# dtmf_v1_2.net
KiCad netlist of a schematic drawn in EAGLE
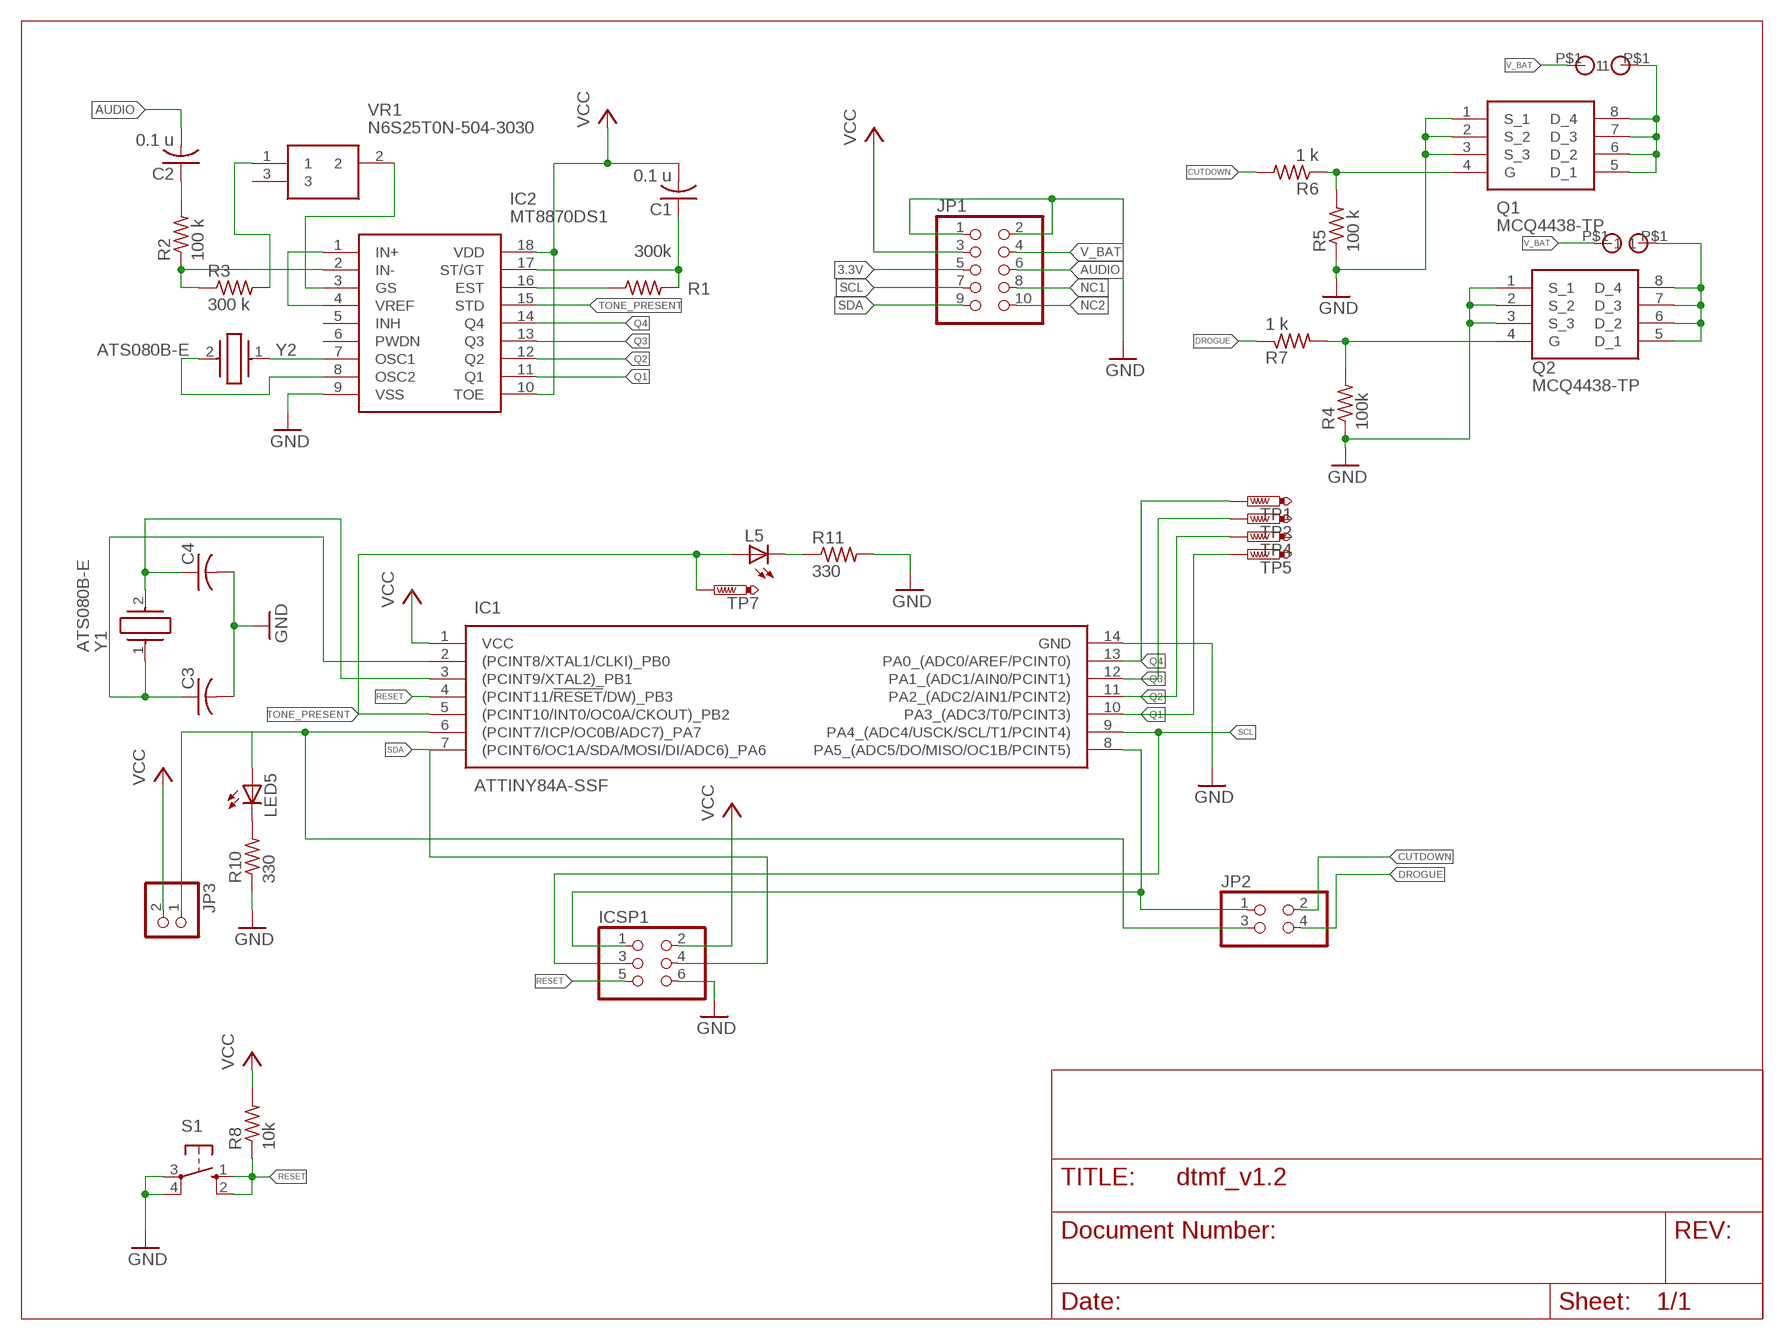
[diagram p0: schematic, sheet 1]

(export (version "E")
  (design (tool "Eeschema 10.0.6"))
  (components
    (comp (ref "C1")
      (value "0.1 u")
      (footprint "eagle-import:C0603")
      (libsource (lib "eagle-import") (part "C-USC0603"))
    )
    (comp (ref "C2")
      (value "0.1 u")
      (footprint "eagle-import:C0603")
      (libsource (lib "eagle-import") (part "C-USC0603"))
    )
    (comp (ref "C3")
      (value "C-USC0805")
      (footprint "eagle-import:C0805")
      (libsource (lib "eagle-import") (part "C-USC0805"))
    )
    (comp (ref "C4")
      (value "C-USC0805")
      (footprint "eagle-import:C0805")
      (libsource (lib "eagle-import") (part "C-USC0805"))
    )
    (comp (ref "IC1")
      (value "ATTINY84A-SSF")
      (footprint "eagle-import:SOIC127P600X175-14N")
      (fields (field (name "MOUSER_PART_NUMBER") "556-ATTINY84A-SSF"))
      (libsource (lib "eagle-import") (part "ATTINY84A-SSF"))
    )
    (comp (ref "IC2")
      (value "MT8870DS1")
      (footprint "eagle-import:SOIC127P1032X265-18N")
      (fields (field (name "MOUSER_PART_NUMBER") "494-MT8870DS1"))
      (libsource (lib "eagle-import") (part "MT8870DS1"))
    )
    (comp (ref "ICSP1")
      (value "PINHD-2X3")
      (footprint "eagle-import:2X03")
      (libsource (lib "eagle-import") (part "PINHD-2X3"))
    )
    (comp (ref "JP1")
      (value "PINHD-2X5")
      (footprint "eagle-import:2X05")
      (libsource (lib "eagle-import") (part "PINHD-2X5"))
    )
    (comp (ref "JP2")
      (value "PINHD-2X2")
      (footprint "eagle-import:2X02")
      (libsource (lib "eagle-import") (part "PINHD-2X2"))
    )
    (comp (ref "JP3")
      (value "PINHD-1X2")
      (footprint "eagle-import:1X02")
      (libsource (lib "eagle-import") (part "PINHD-1X2"))
    )
    (comp (ref "L5")
      (value "LEDCHIP-LED0805")
      (footprint "eagle-import:CHIP-LED0805")
      (libsource (lib "eagle-import") (part "LEDCHIP-LED0805"))
    )
    (comp (ref "LED5")
      (value "LEDCHIP-LED0805")
      (footprint "eagle-import:CHIP-LED0805")
      (libsource (lib "eagle-import") (part "LEDCHIP-LED0805"))
    )
    (comp (ref "Q1")
      (value "MCQ4438-TP")
      (footprint "eagle-import:SOIC127P600X175-8N")
      (libsource (lib "eagle-import") (part "MCQ4438-TP"))
    )
    (comp (ref "Q2")
      (value "MCQ4438-TP")
      (footprint "eagle-import:SOIC127P600X175-8N")
      (libsource (lib "eagle-import") (part "MCQ4438-TP"))
    )
    (comp (ref "R1")
      (value "300k")
      (footprint "eagle-import:M0805")
      (libsource (lib "eagle-import") (part "R-US_M0805"))
    )
    (comp (ref "R2")
      (value "100 k")
      (footprint "eagle-import:M0805")
      (libsource (lib "eagle-import") (part "R-US_M0805"))
    )
    (comp (ref "R3")
      (value "300 k")
      (footprint "eagle-import:M0805")
      (libsource (lib "eagle-import") (part "R-US_M0805"))
    )
    (comp (ref "R4")
      (value "100k")
      (footprint "eagle-import:M0805")
      (libsource (lib "eagle-import") (part "R-US_M0805"))
    )
    (comp (ref "R5")
      (value "100 k")
      (footprint "eagle-import:M0805")
      (libsource (lib "eagle-import") (part "R-US_M0805"))
    )
    (comp (ref "R6")
      (value "1 k")
      (footprint "eagle-import:M0805")
      (libsource (lib "eagle-import") (part "R-US_M0805"))
    )
    (comp (ref "R7")
      (value "1 k")
      (footprint "eagle-import:M0805")
      (libsource (lib "eagle-import") (part "R-US_M0805"))
    )
    (comp (ref "R8")
      (value "10k")
      (footprint "eagle-import:0207_10")
      (libsource (lib "eagle-import") (part "R-US_0207/10"))
    )
    (comp (ref "R10")
      (value "330")
      (footprint "eagle-import:M0805")
      (libsource (lib "eagle-import") (part "R-US_M0805"))
    )
    (comp (ref "R11")
      (value "330")
      (footprint "eagle-import:M0805")
      (libsource (lib "eagle-import") (part "R-US_M0805"))
    )
    (comp (ref "S1")
      (value "10-XX")
      (footprint "eagle-import:B3F-10XX")
      (fields (field (name "MPN") "B3F-1000"))
      (libsource (lib "eagle-import") (part "10-XX"))
    )
    (comp (ref "TP1")
      (value "PTR1B1,27")
      (footprint "eagle-import:B1,27")
      (libsource (lib "eagle-import") (part "PTR1B1,27"))
    )
    (comp (ref "TP2")
      (value "PTR1B1,27")
      (footprint "eagle-import:B1,27")
      (libsource (lib "eagle-import") (part "PTR1B1,27"))
    )
    (comp (ref "TP4")
      (value "PTR1B1,27")
      (footprint "eagle-import:B1,27")
      (libsource (lib "eagle-import") (part "PTR1B1,27"))
    )
    (comp (ref "TP5")
      (value "PTR1B1,27")
      (footprint "eagle-import:B1,27")
      (libsource (lib "eagle-import") (part "PTR1B1,27"))
    )
    (comp (ref "TP7")
      (value "PTR1B1,27")
      (footprint "eagle-import:B1,27")
      (libsource (lib "eagle-import") (part "PTR1B1,27"))
    )
    (comp (ref "U$1")
      (value "M3_HOLE")
      (footprint "eagle-import:MOUNTING_PAD")
      (libsource (lib "eagle-import") (part "M3_HOLE"))
    )
    (comp (ref "U$2")
      (value "M3_HOLE")
      (footprint "eagle-import:MOUNTING_PAD")
      (libsource (lib "eagle-import") (part "M3_HOLE"))
    )
    (comp (ref "U$3")
      (value "M3_HOLE")
      (footprint "eagle-import:MOUNTING_PAD")
      (libsource (lib "eagle-import") (part "M3_HOLE"))
    )
    (comp (ref "U$4")
      (value "M3_HOLE")
      (footprint "eagle-import:MOUNTING_PAD")
      (libsource (lib "eagle-import") (part "M3_HOLE"))
    )
    (comp (ref "VR1")
      (value "N6S25T0N-504-3030")
      (footprint "eagle-import:N6S25T0N5043030")
      (fields (field (name "MOUSER_PART_NUMBER") "531-N6S25T0N5043030"))
      (libsource (lib "eagle-import") (part "N6S25T0N-504-3030"))
    )
    (comp (ref "Y1")
      (value "ATS080B-E")
      (footprint "eagle-import:ATS080BE")
      (fields (field (name "MOUSER_PART_NUMBER") "774-ATS080B-E"))
      (libsource (lib "eagle-import") (part "ATS080B-E"))
    )
    (comp (ref "Y2")
      (value "ATS080B-E")
      (footprint "eagle-import:ATS080BE")
      (fields (field (name "MOUSER_PART_NUMBER") "774-ATS080B-E"))
      (libsource (lib "eagle-import") (part "ATS080B-E"))
    )
  )
  (nets
    (net (code "1") (name "3.3V") (class "Default")
      (node (ref "JP1") (pin "5") (pinfunction "5_5") (pintype "passive"))
    )
    (net (code "2") (name "AUDIO") (class "Default")
      (node (ref "C2") (pin "2") (pinfunction "2_2") (pintype "passive"))
      (node (ref "JP1") (pin "6") (pinfunction "6_6") (pintype "passive"))
    )
    (net (code "3") (name "CUTDOWN") (class "Default")
      (node (ref "JP2") (pin "2") (pinfunction "2_2") (pintype "passive"))
      (node (ref "R6") (pin "2") (pinfunction "2_2") (pintype "passive"))
    )
    (net (code "4") (name "DROGUE") (class "Default")
      (node (ref "JP2") (pin "4") (pinfunction "4_4") (pintype "passive"))
      (node (ref "R7") (pin "1") (pinfunction "1_1") (pintype "passive"))
    )
    (net (code "5") (name "GND") (class "Default")
      (node (ref "C3") (pin "2") (pinfunction "2_2") (pintype "passive"))
      (node (ref "C4") (pin "2") (pinfunction "2_2") (pintype "passive"))
      (node (ref "IC1") (pin "14") (pinfunction "GND_14") (pintype "bidirectional"))
      (node (ref "IC2") (pin "9") (pinfunction "VSS_9") (pintype "bidirectional"))
      (node (ref "ICSP1") (pin "6") (pinfunction "6_6") (pintype "passive"))
      (node (ref "JP1") (pin "1") (pinfunction "1_1") (pintype "passive"))
      (node (ref "JP1") (pin "2") (pinfunction "2_2") (pintype "passive"))
      (node (ref "Q1") (pin "1") (pinfunction "S_1_1") (pintype "bidirectional"))
      (node (ref "Q1") (pin "2") (pinfunction "S_2_2") (pintype "bidirectional"))
      (node (ref "Q1") (pin "3") (pinfunction "S_3_3") (pintype "bidirectional"))
      (node (ref "Q2") (pin "1") (pinfunction "S_1_1") (pintype "bidirectional"))
      (node (ref "Q2") (pin "2") (pinfunction "S_2_2") (pintype "bidirectional"))
      (node (ref "Q2") (pin "3") (pinfunction "S_3_3") (pintype "bidirectional"))
      (node (ref "R10") (pin "1") (pinfunction "1_1") (pintype "passive"))
      (node (ref "R11") (pin "2") (pinfunction "2_2") (pintype "passive"))
      (node (ref "R4") (pin "1") (pinfunction "1_1") (pintype "passive"))
      (node (ref "R5") (pin "1") (pinfunction "1_1") (pintype "passive"))
      (node (ref "S1") (pin "3") (pinfunction "P_3") (pintype "passive"))
      (node (ref "S1") (pin "4") (pinfunction "P1_4") (pintype "passive"))
    )
    (net (code "6") (name "NC1") (class "Default")
      (node (ref "JP1") (pin "8") (pinfunction "8_8") (pintype "passive"))
    )
    (net (code "7") (name "NC2") (class "Default")
      (node (ref "JP1") (pin "10") (pinfunction "10_10") (pintype "passive"))
    )
    (net (code "8") (name "Net-(C2-Pad1)") (class "Default")
      (node (ref "C2") (pin "1") (pinfunction "1_1") (pintype "passive"))
      (node (ref "R2") (pin "2") (pinfunction "2_2") (pintype "passive"))
    )
    (net (code "9") (name "Net-(IC1-(PCINT7{slash}ICP{slash}OC0B{slash}ADC7)_PA7)") (class "Default")
      (node (ref "IC1") (pin "6") (pinfunction "(PCINT7/ICP/OC0B/ADC7)_PA7_6") (pintype "bidirectional"))
      (node (ref "JP2") (pin "3") (pinfunction "3_3") (pintype "passive"))
      (node (ref "JP3") (pin "1") (pinfunction "1_1") (pintype "passive"))
      (node (ref "LED5") (pin "A") (pinfunction "A_A") (pintype "passive"))
    )
    (net (code "10") (name "Net-(IC1-(PCINT8{slash}XTAL1{slash}CLKI)_PB0)") (class "Default")
      (node (ref "C3") (pin "1") (pinfunction "1_1") (pintype "passive"))
      (node (ref "IC1") (pin "2") (pinfunction "(PCINT8/XTAL1/CLKI)_PB0_2") (pintype "bidirectional"))
      (node (ref "Y1") (pin "1") (pinfunction "1_1") (pintype "bidirectional"))
    )
    (net (code "11") (name "Net-(IC1-(PCINT9{slash}XTAL2)_PB1)") (class "Default")
      (node (ref "C4") (pin "1") (pinfunction "1_1") (pintype "passive"))
      (node (ref "IC1") (pin "3") (pinfunction "(PCINT9/XTAL2)_PB1_3") (pintype "bidirectional"))
      (node (ref "Y1") (pin "2") (pinfunction "2_2") (pintype "bidirectional"))
    )
    (net (code "12") (name "Net-(IC1-PA5_(ADC5{slash}DO{slash}MISO{slash}OC1B{slash}PCINT5))") (class "Default")
      (node (ref "IC1") (pin "8") (pinfunction "PA5_(ADC5/DO/MISO/OC1B/PCINT5)_8") (pintype "bidirectional"))
      (node (ref "ICSP1") (pin "1") (pinfunction "1_1") (pintype "passive"))
      (node (ref "JP2") (pin "1") (pinfunction "1_1") (pintype "passive"))
    )
    (net (code "13") (name "Net-(IC2-EST)") (class "Default")
      (node (ref "IC2") (pin "16") (pinfunction "EST_16") (pintype "bidirectional"))
      (node (ref "R1") (pin "1") (pinfunction "1_1") (pintype "passive"))
    )
    (net (code "14") (name "Net-(IC2-GS)") (class "Default")
      (node (ref "IC2") (pin "3") (pinfunction "GS_3") (pintype "bidirectional"))
      (node (ref "VR1") (pin "2") (pinfunction "2_2") (pintype "bidirectional"))
    )
    (net (code "15") (name "Net-(IC2-IN+)") (class "Default")
      (node (ref "IC2") (pin "1") (pinfunction "IN+_1") (pintype "bidirectional"))
      (node (ref "IC2") (pin "4") (pinfunction "VREF_4") (pintype "bidirectional"))
    )
    (net (code "16") (name "Net-(IC2-IN-)") (class "Default")
      (node (ref "IC2") (pin "2") (pinfunction "IN-_2") (pintype "bidirectional"))
      (node (ref "R2") (pin "1") (pinfunction "1_1") (pintype "passive"))
      (node (ref "R3") (pin "1") (pinfunction "1_1") (pintype "passive"))
    )
    (net (code "17") (name "Net-(IC2-OSC1)") (class "Default")
      (node (ref "IC2") (pin "7") (pinfunction "OSC1_7") (pintype "bidirectional"))
      (node (ref "Y2") (pin "1") (pinfunction "1_1") (pintype "bidirectional"))
    )
    (net (code "18") (name "Net-(IC2-OSC2)") (class "Default")
      (node (ref "IC2") (pin "8") (pinfunction "OSC2_8") (pintype "bidirectional"))
      (node (ref "Y2") (pin "2") (pinfunction "2_2") (pintype "bidirectional"))
    )
    (net (code "19") (name "Net-(IC2-ST{slash}GT)") (class "Default")
      (node (ref "C1") (pin "1") (pinfunction "1_1") (pintype "passive"))
      (node (ref "IC2") (pin "17") (pinfunction "ST/GT_17") (pintype "bidirectional"))
      (node (ref "R1") (pin "2") (pinfunction "2_2") (pintype "passive"))
    )
    (net (code "20") (name "Net-(L5-PadC)") (class "Default")
      (node (ref "L5") (pin "C") (pinfunction "C_C") (pintype "passive"))
      (node (ref "R11") (pin "1") (pinfunction "1_1") (pintype "passive"))
    )
    (net (code "21") (name "Net-(LED5-PadC)") (class "Default")
      (node (ref "LED5") (pin "C") (pinfunction "C_C") (pintype "passive"))
      (node (ref "R10") (pin "2") (pinfunction "2_2") (pintype "passive"))
    )
    (net (code "22") (name "Net-(Q1-D_1)") (class "Default")
      (node (ref "Q1") (pin "5") (pinfunction "D_1_5") (pintype "bidirectional"))
      (node (ref "Q1") (pin "6") (pinfunction "D_2_6") (pintype "bidirectional"))
      (node (ref "Q1") (pin "7") (pinfunction "D_3_7") (pintype "bidirectional"))
      (node (ref "Q1") (pin "8") (pinfunction "D_4_8") (pintype "bidirectional"))
      (node (ref "U$2") (pin "P$1") (pinfunction "1_P$1") (pintype "bidirectional"))
    )
    (net (code "23") (name "Net-(Q1-G)") (class "Default")
      (node (ref "Q1") (pin "4") (pinfunction "G_4") (pintype "bidirectional"))
      (node (ref "R5") (pin "2") (pinfunction "2_2") (pintype "passive"))
      (node (ref "R6") (pin "1") (pinfunction "1_1") (pintype "passive"))
    )
    (net (code "24") (name "Net-(Q2-D_1)") (class "Default")
      (node (ref "Q2") (pin "5") (pinfunction "D_1_5") (pintype "bidirectional"))
      (node (ref "Q2") (pin "6") (pinfunction "D_2_6") (pintype "bidirectional"))
      (node (ref "Q2") (pin "7") (pinfunction "D_3_7") (pintype "bidirectional"))
      (node (ref "Q2") (pin "8") (pinfunction "D_4_8") (pintype "bidirectional"))
      (node (ref "U$4") (pin "P$1") (pinfunction "1_P$1") (pintype "bidirectional"))
    )
    (net (code "25") (name "Net-(Q2-G)") (class "Default")
      (node (ref "Q2") (pin "4") (pinfunction "G_4") (pintype "bidirectional"))
      (node (ref "R4") (pin "2") (pinfunction "2_2") (pintype "passive"))
      (node (ref "R7") (pin "2") (pinfunction "2_2") (pintype "passive"))
    )
    (net (code "26") (name "Net-(R3-Pad2)") (class "Default")
      (node (ref "R3") (pin "2") (pinfunction "2_2") (pintype "passive"))
      (node (ref "VR1") (pin "1") (pinfunction "1_1") (pintype "bidirectional"))
    )
    (net (code "27") (name "Q1") (class "Default")
      (node (ref "IC1") (pin "10") (pinfunction "PA3_(ADC3/T0/PCINT3)_10") (pintype "bidirectional"))
      (node (ref "IC2") (pin "11") (pinfunction "Q1_11") (pintype "bidirectional"))
      (node (ref "TP5") (pin "TP") (pinfunction "TP_TP") (pintype "input"))
    )
    (net (code "28") (name "Q2") (class "Default")
      (node (ref "IC1") (pin "11") (pinfunction "PA2_(ADC2/AIN1/PCINT2)_11") (pintype "bidirectional"))
      (node (ref "IC2") (pin "12") (pinfunction "Q2_12") (pintype "bidirectional"))
      (node (ref "TP4") (pin "TP") (pinfunction "TP_TP") (pintype "input"))
    )
    (net (code "29") (name "Q3") (class "Default")
      (node (ref "IC1") (pin "12") (pinfunction "PA1_(ADC1/AIN0/PCINT1)_12") (pintype "bidirectional"))
      (node (ref "IC2") (pin "13") (pinfunction "Q3_13") (pintype "bidirectional"))
      (node (ref "TP2") (pin "TP") (pinfunction "TP_TP") (pintype "input"))
    )
    (net (code "30") (name "Q4") (class "Default")
      (node (ref "IC1") (pin "13") (pinfunction "PA0_(ADC0/AREF/PCINT0)_13") (pintype "bidirectional"))
      (node (ref "IC2") (pin "14") (pinfunction "Q4_14") (pintype "bidirectional"))
      (node (ref "TP1") (pin "TP") (pinfunction "TP_TP") (pintype "input"))
    )
    (net (code "31") (name "RESET") (class "Default")
      (node (ref "IC1") (pin "4") (pinfunction "(PCINT11/~{RESET}/DW)_PB3_4") (pintype "bidirectional"))
      (node (ref "ICSP1") (pin "5") (pinfunction "5_5") (pintype "passive"))
      (node (ref "R8") (pin "1") (pinfunction "1_1") (pintype "passive"))
      (node (ref "S1") (pin "1") (pinfunction "S_1") (pintype "passive"))
      (node (ref "S1") (pin "2") (pinfunction "S1_2") (pintype "passive"))
    )
    (net (code "32") (name "SCL") (class "Default")
      (node (ref "IC1") (pin "9") (pinfunction "PA4_(ADC4/USCK/SCL/T1/PCINT4)_9") (pintype "bidirectional"))
      (node (ref "ICSP1") (pin "3") (pinfunction "3_3") (pintype "passive"))
      (node (ref "JP1") (pin "7") (pinfunction "7_7") (pintype "passive"))
    )
    (net (code "33") (name "SDA") (class "Default")
      (node (ref "IC1") (pin "7") (pinfunction "(PCINT6/OC1A/SDA/MOSI/DI/ADC6)_PA6_7") (pintype "bidirectional"))
      (node (ref "ICSP1") (pin "4") (pinfunction "4_4") (pintype "passive"))
      (node (ref "JP1") (pin "9") (pinfunction "9_9") (pintype "passive"))
    )
    (net (code "34") (name "TONE_PRESENT") (class "Default")
      (node (ref "IC1") (pin "5") (pinfunction "(PCINT10/INT0/OC0A/CKOUT)_PB2_5") (pintype "bidirectional"))
      (node (ref "IC2") (pin "15") (pinfunction "STD_15") (pintype "bidirectional"))
      (node (ref "L5") (pin "A") (pinfunction "A_A") (pintype "passive"))
      (node (ref "TP7") (pin "TP") (pinfunction "TP_TP") (pintype "input"))
    )
    (net (code "35") (name "VCC") (class "Default")
      (node (ref "C1") (pin "2") (pinfunction "2_2") (pintype "passive"))
      (node (ref "IC1") (pin "1") (pinfunction "VCC_1") (pintype "bidirectional"))
      (node (ref "IC2") (pin "10") (pinfunction "TOE_10") (pintype "bidirectional"))
      (node (ref "IC2") (pin "18") (pinfunction "VDD_18") (pintype "bidirectional"))
      (node (ref "ICSP1") (pin "2") (pinfunction "2_2") (pintype "passive"))
      (node (ref "JP1") (pin "3") (pinfunction "3_3") (pintype "passive"))
      (node (ref "JP3") (pin "2") (pinfunction "2_2") (pintype "passive"))
      (node (ref "R8") (pin "2") (pinfunction "2_2") (pintype "passive"))
    )
    (net (code "36") (name "V_BAT") (class "Default")
      (node (ref "JP1") (pin "4") (pinfunction "4_4") (pintype "passive"))
      (node (ref "U$1") (pin "P$1") (pinfunction "1_P$1") (pintype "bidirectional"))
      (node (ref "U$3") (pin "P$1") (pinfunction "1_P$1") (pintype "bidirectional"))
    )
    (net (code "37") (name "unconnected-(IC2-INH-Pad5)") (class "Default")
      (node (ref "IC2") (pin "5") (pinfunction "INH_5") (pintype "bidirectional"))
    )
    (net (code "38") (name "unconnected-(IC2-PWDN-Pad6)") (class "Default")
      (node (ref "IC2") (pin "6") (pinfunction "PWDN_6") (pintype "bidirectional"))
    )
    (net (code "39") (name "unconnected-(VR1-Pad3)") (class "Default")
      (node (ref "VR1") (pin "3") (pinfunction "3_3") (pintype "bidirectional"))
    )
  )
)
